# power-v5v5n.net
KiCad netlist of a schematic drawn in Altium Designer
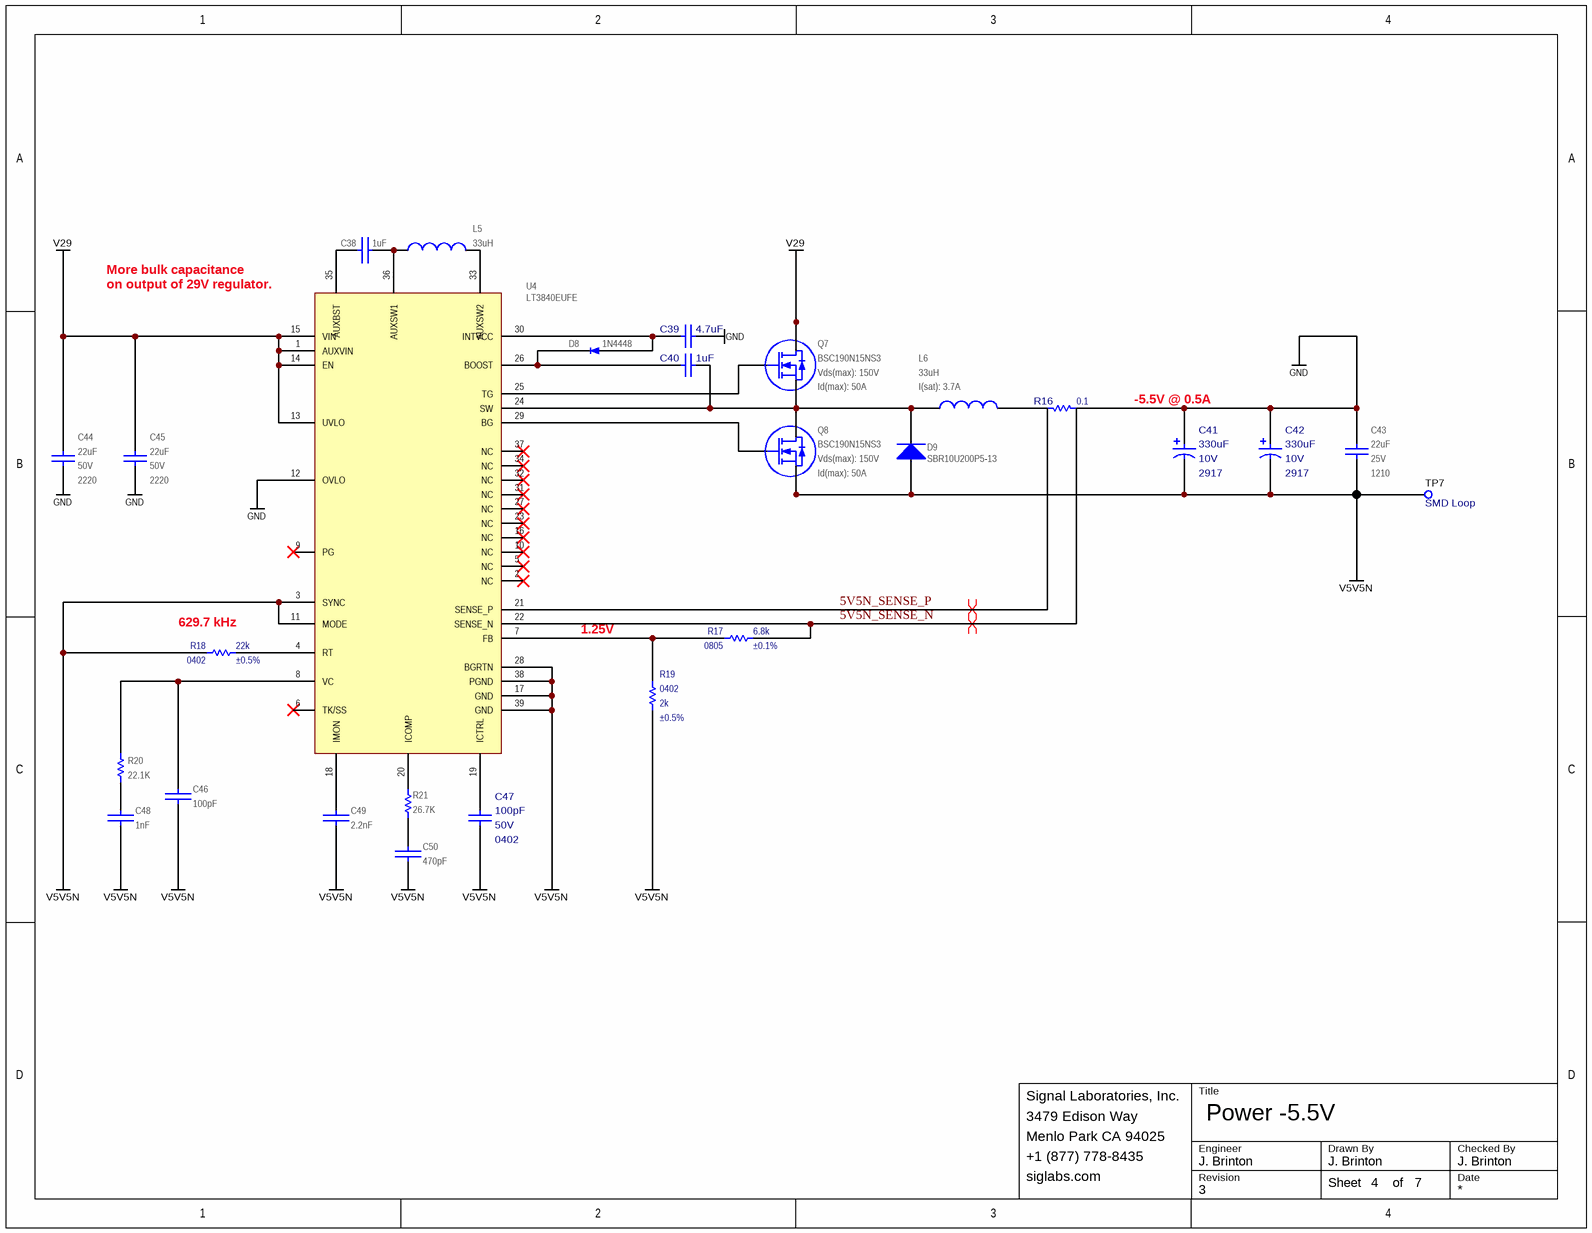
[diagram p0: power-v5v5n.SchDoc]

(export (version "E")
  (design (tool "Eeschema 10.0.6"))
  (components
    (comp (ref "C38")
      (value "1uF")
      (footprint "CAPC100X50X55L25N")
      (description "Ceramic Capacitor 1uF ±10% 10V X5R 0402")
      (fields (field (name "MANUFACTURER") "Murata") (field (name "TOLERANCE") "±10%"))
      (libsource (lib "*") (part "CAP"))
    )
    (comp (ref "C39")
      (value "4.7uF")
      (footprint "CAPC160X80X90L20NA")
      (description "Ceramic Capacitor 4.7uF ±10% 25V X5R 0603")
      (fields (field (name "MANUFACTURER") "Samsung") (field (name "TOLERANCE") "±10%"))
      (libsource (lib "capacitors") (part "CAP"))
    )
    (comp (ref "C40")
      (value "1uF")
      (footprint "CAPC100X50X55L25N")
      (description "Ceramic Capacitor 1uF ±10% 10V X5R 0402")
      (fields (field (name "MANUFACTURER") "Murata") (field (name "TOLERANCE") "±10%"))
      (libsource (lib "capacitors") (part "CAP"))
    )
    (comp (ref "C41")
      (value "330uF")
      (footprint "CAPPM730X435X310L135X240N")
      (description "Tantalum Capacitor 330uF ±10% 10V 2917")
      (fields
        (field (name "MANUFACTURER") "AVX")
        (field (name "TOLERANCE") "±10%")
        (field (name "PACKAGE") "2917")
        (field (name "VOLTAGE") "10V")
      )
      (libsource (lib "avx") (part "CAP_POL"))
    )
    (comp (ref "C42")
      (value "330uF")
      (footprint "CAPPM730X435X310L135X240N")
      (description "Tantalum Capacitor 330uF ±10% 10V 2917")
      (fields
        (field (name "MANUFACTURER") "AVX")
        (field (name "TOLERANCE") "±10%")
        (field (name "PACKAGE") "2917")
        (field (name "VOLTAGE") "10V")
      )
      (libsource (lib "avx") (part "CAP_POL"))
    )
    (comp (ref "C43")
      (value "22uF")
      (footprint "CAPC320X250X270L50N")
      (description "Ceramic Capacitor 22uF ±10% 25V X7R 1210")
      (fields
        (field (name "MANUFACTURER") "Murata")
        (field (name "TOLERANCE") "±10%")
        (field (name "VOLTAGE") "25V")
        (field (name "PACKAGE") "1210")
      )
      (libsource (lib "generic") (part "CAP"))
    )
    (comp (ref "C44")
      (value "22uF")
      (footprint "CAPC600X500X500L160N")
      (description "Ceramic Capacitor 22uF ±20% 50V X7S Stacked")
      (fields
        (field (name "MANUFACTURER") "TDK")
        (field (name "TOLERANCE") "±20%")
        (field (name "VOLTAGE") "50V")
        (field (name "PACKAGE") "2220")
      )
      (libsource (lib "generic") (part "CAP"))
    )
    (comp (ref "C45")
      (value "22uF")
      (footprint "CAPC600X500X500L160N")
      (description "Ceramic Capacitor 22uF ±20% 50V X7S Stacked")
      (fields
        (field (name "MANUFACTURER") "TDK")
        (field (name "TOLERANCE") "±20%")
        (field (name "VOLTAGE") "50V")
        (field (name "PACKAGE") "2220")
      )
      (libsource (lib "generic") (part "CAP"))
    )
    (comp (ref "C46")
      (value "100pF")
      (footprint "CAPC100X50X55L25N")
      (description "Ceramic Capacitor 100pF ±1% 50V NP0 0402")
      (fields (field (name "MANUFACTURER") "Murata") (field (name "VOLTAGE") "50V"))
      (libsource (lib "*") (part "CAP"))
    )
    (comp (ref "C47")
      (value "100pF")
      (footprint "generic:CAPC100X50X55L25N")
      (description "Ceramic Capacitor 100pF ±10% 50V C0G 0402")
      (fields
        (field (name "MANUFACTURER") "Vishay")
        (field (name "TOLERANCE") "±10%")
        (field (name "PACKAGE") "0402")
        (field (name "VOLTAGE") "50V")
      )
      (libsource (lib "capacitors") (part "CAP"))
    )
    (comp (ref "C48")
      (value "1nF")
      (footprint "CAPC100X50X55L25N")
      (description "Ceramic Capacitor 1nF ±5% 50V NP0 0402")
      (fields (field (name "MANUFACTURER") "Murata") (field (name "VOLTAGE") "50V"))
      (libsource (lib "*") (part "CAP"))
    )
    (comp (ref "C49")
      (value "2.2nF")
      (footprint "CAPC100X50X55L25N")
      (description "Ceramic Capacitor 2.2nF ±5% 25V NP0 0402")
      (fields (field (name "MANUFACTURER") "Kemet") (field (name "TOLERANCE") "±5%"))
      (libsource (lib "*") (part "CAP"))
    )
    (comp (ref "C50")
      (value "470pF")
      (footprint "CAPC100X50X55L25N")
      (description "Ceramic Capacitor 470pF ±5% 50V X7R 0402")
      (fields (field (name "MANUFACTURER") "Murata") (field (name "VOLTAGE") "50V"))
      (libsource (lib "*") (part "CAP"))
    )
    (comp (ref "D8")
      (value "1N4448HWS-7-F")
      (footprint "diodes_inc:SOD323")
      (description "Schottky Diode 80V 250mA SOD323")
      (fields (field (name "MANUFACTURER") "Diodes Inc") (field (name "ALTERNATIVE P/N") "1N4448"))
      (libsource (lib "diodes_inc") (part "1N4448HWS-7-F"))
    )
    (comp (ref "D9")
      (value "SBR10U200P5-13")
      (footprint "DIODES_POWERDI5")
      (description "Schottky Diode 200V 10A SMD")
      (fields (field (name "MANUFACTURER") "Diodes Inc"))
      (libsource (lib "diodes_inc") (part "PDS5100H"))
    )
    (comp (ref "L5")
      (value "33uH")
      (footprint "coilcraft:ME3220")
      (description "Inductor 33uH ±10% 500mA SMD")
      (fields (field (name "MANUFACTURER") "Coilcraft") (field (name "TOLERANCE") "±10%"))
      (libsource (lib "CamBoard_Pico_70.19K") (part "COIL"))
    )
    (comp (ref "L6")
      (value "33uH")
      (footprint "coilcraft:XAL6060")
      (description "Inductor 33uH,3.7A(sat), SMD")
      (fields
        (field (name "MANUFACTURER") "Coilcraft")
        (field (name "I(SAT)") "3.7A")
        (field (name "Comment") "XAL6060-333ME")
      )
      (libsource (lib "CamBoard_Pico_70.19K") (part "COIL"))
    )
    (comp (ref "Q7")
      (value "BSC190N15NS3")
      (footprint "TDSON-8")
      (description "MOSFET N-Channel Enhancement Mode")
      (fields
        (field (name "MANUFACTURER") "Infineon")
        (field (name "VDS(MAX)") "150V")
        (field (name "ID(MAX)") "50A")
      )
      (libsource (lib "infinion") (part "BSC190N15NS3"))
    )
    (comp (ref "Q8")
      (value "BSC190N15NS3")
      (footprint "TDSON-8")
      (description "MOSFET N-Channel Enhancement Mode")
      (fields
        (field (name "MANUFACTURER") "Infineon")
        (field (name "VDS(MAX)") "150V")
        (field (name "ID(MAX)") "50A")
      )
      (libsource (lib "infinion") (part "BSC190N15NS3"))
    )
    (comp (ref "R16")
      (value "0.1")
      (footprint "susumu:KRL3216T4")
      (description "Current Sense Resistor 100 mOhms +/-1% SMD 4-Terminal")
      (fields (field (name "TOLERANCE") "±1%") (field (name "MANUFACTURER") "Susumu"))
      (libsource (lib "susumu") (part "KRL3216T4A-M-R009-F"))
    )
    (comp (ref "R17")
      (value "6.8k")
      (footprint "RESC2012X70N")
      (description "Thin Film Resistor 6.8k +/-0.1% SMD 0805")
      (fields
        (field (name "TOLERANCE") "±0.1%")
        (field (name "MANUFACTURER") "Susumu")
        (field (name "PACKAGE") "0805")
        (field (name "Comment") "RG2012P-682-B-T5")
      )
      (libsource (lib "generic") (part "RES"))
    )
    (comp (ref "R18")
      (value "22k")
      (footprint "RESC1005X40N")
      (description "Thin Film Resistor 22k +/-0.5% SMD 0402")
      (fields
        (field (name "TOLERANCE") "±0.5%")
        (field (name "MANUFACTURER") "Susumu")
        (field (name "PACKAGE") "0402")
        (field (name "Comment") "RR0510P-223-D")
      )
      (libsource (lib "generic") (part "RES"))
    )
    (comp (ref "R19")
      (value "2k")
      (footprint "RESC1005X40N")
      (description "Thin Film Resistor 2k +/-0.5% SMD 0402")
      (fields
        (field (name "TOLERANCE") "±0.5%")
        (field (name "MANUFACTURER") "Susumu")
        (field (name "PACKAGE") "0402")
        (field (name "Comment") "RR0510P-202-D")
      )
      (libsource (lib "generic") (part "RES"))
    )
    (comp (ref "R20")
      (value "22.1K")
      (footprint "generic:RESC1005X40N")
      (description "Thick Film Resistor 22.1k ±1% 0402")
      (fields (field (name "MANUFACTURER") "Panasonic") (field (name "TOLERANCE") "±1%"))
      (libsource (lib "Graviton") (part "RES 0402"))
    )
    (comp (ref "R21")
      (value "26.7K")
      (footprint "generic:RESC1005X40N")
      (description "Thick Film Resistor 26.7k ±1% 0402")
      (fields (field (name "MANUFACTURER") "Panasonic") (field (name "TOLERANCE") "±1%"))
      (libsource (lib "Graviton") (part "RES 0402"))
    )
    (comp (ref "TP7")
      (value "5015")
      (footprint "keystone:5015")
      (description "Test Point SMD")
      (fields (field (name "MANUFACTURER") "Keystone") (field (name "NOTES") "SMD Loop"))
      (libsource (lib "generic") (part "TEST_POINT_SMD_50"))
    )
    (comp (ref "U4")
      (value "LT3840EUFE")
      (footprint "linear:QFN39P40_600X400X80L40X20T465X265N")
      (description "Synchronous Regulator Controller")
      (fields (field (name "MANUFACTURER") "Linear Technology"))
      (libsource (lib "linear") (part "LT3840EUFE"))
    )
  )
  (nets
    (net (code "1") (name "/5V5N_SENSE_N") (class "Default")
      (node (ref "R16") (pin "4") (pinfunction "4_4") (pintype "passive"))
      (node (ref "R17") (pin "1") (pinfunction "1_1") (pintype "passive"))
      (node (ref "U4") (pin "22") (pinfunction "SENSE_N_22") (pintype "passive"))
    )
    (net (code "2") (name "/5V5N_SENSE_P") (class "Default")
      (node (ref "R16") (pin "3") (pinfunction "3_3") (pintype "passive"))
      (node (ref "U4") (pin "21") (pinfunction "SENSE_P_21") (pintype "passive"))
    )
    (net (code "3") (name "GND") (class "Default")
      (node (ref "C39") (pin "2") (pinfunction "2_2") (pintype "passive"))
      (node (ref "C41") (pin "1") (pinfunction "1_1") (pintype "passive"))
      (node (ref "C42") (pin "1") (pinfunction "1_1") (pintype "passive"))
      (node (ref "C43") (pin "2") (pinfunction "2_2") (pintype "passive"))
      (node (ref "C44") (pin "1") (pinfunction "1_1") (pintype "passive"))
      (node (ref "C45") (pin "1") (pinfunction "1_1") (pintype "passive"))
      (node (ref "R16") (pin "2") (pinfunction "2_2") (pintype "passive"))
      (node (ref "U4") (pin "12") (pinfunction "OVLO_12") (pintype "passive"))
    )
    (net (code "4") (name "Net-(C48-Pad1)") (class "Default")
      (node (ref "C48") (pin "1") (pinfunction "1_1") (pintype "passive"))
      (node (ref "R20") (pin "1") (pinfunction "1_1") (pintype "passive"))
    )
    (net (code "5") (name "Net-(C50-Pad2)") (class "Default")
      (node (ref "C50") (pin "2") (pinfunction "2_2") (pintype "passive"))
      (node (ref "R21") (pin "2") (pinfunction "2_2") (pintype "passive"))
    )
    (net (code "6") (name "Net-(L6-Pad2)") (class "Default")
      (node (ref "L6") (pin "2") (pinfunction "2_2") (pintype "passive"))
      (node (ref "R16") (pin "1") (pinfunction "1_1") (pintype "passive"))
    )
    (net (code "7") (name "Net-(Q7-G)") (class "Default")
      (node (ref "Q7") (pin "4") (pinfunction "G_4") (pintype "passive"))
      (node (ref "U4") (pin "25") (pinfunction "TG_25") (pintype "passive"))
    )
    (net (code "8") (name "Net-(Q8-G)") (class "Default")
      (node (ref "Q8") (pin "4") (pinfunction "G_4") (pintype "passive"))
      (node (ref "U4") (pin "29") (pinfunction "BG_29") (pintype "passive"))
    )
    (net (code "9") (name "Net-(U4-AUXBST)") (class "Default")
      (node (ref "C38") (pin "2") (pinfunction "2_2") (pintype "passive"))
      (node (ref "U4") (pin "35") (pinfunction "AUXBST_35") (pintype "passive"))
    )
    (net (code "10") (name "Net-(U4-AUXSW1)") (class "Default")
      (node (ref "C38") (pin "1") (pinfunction "1_1") (pintype "passive"))
      (node (ref "L5") (pin "1") (pinfunction "1_1") (pintype "passive"))
      (node (ref "U4") (pin "36") (pinfunction "AUXSW1_36") (pintype "passive"))
    )
    (net (code "11") (name "Net-(U4-AUXSW2)") (class "Default")
      (node (ref "L5") (pin "2") (pinfunction "2_2") (pintype "passive"))
      (node (ref "U4") (pin "33") (pinfunction "AUXSW2_33") (pintype "passive"))
    )
    (net (code "12") (name "Net-(U4-BOOST)") (class "Default")
      (node (ref "C40") (pin "1") (pinfunction "1_1") (pintype "passive"))
      (node (ref "D8") (pin "K") (pinfunction "K_K") (pintype "passive"))
      (node (ref "U4") (pin "26") (pinfunction "BOOST_26") (pintype "passive"))
    )
    (net (code "13") (name "Net-(U4-FB)") (class "Default")
      (node (ref "R17") (pin "2") (pinfunction "2_2") (pintype "passive"))
      (node (ref "R19") (pin "2") (pinfunction "2_2") (pintype "passive"))
      (node (ref "U4") (pin "7") (pinfunction "FB_7") (pintype "passive"))
    )
    (net (code "14") (name "Net-(U4-ICOMP)") (class "Default")
      (node (ref "R21") (pin "1") (pinfunction "1_1") (pintype "passive"))
      (node (ref "U4") (pin "20") (pinfunction "ICOMP_20") (pintype "passive"))
    )
    (net (code "15") (name "Net-(U4-ICTRL)") (class "Default")
      (node (ref "C47") (pin "1") (pinfunction "1_1") (pintype "passive"))
      (node (ref "U4") (pin "19") (pinfunction "ICTRL_19") (pintype "passive"))
    )
    (net (code "16") (name "Net-(U4-IMON)") (class "Default")
      (node (ref "C49") (pin "1") (pinfunction "1_1") (pintype "passive"))
      (node (ref "U4") (pin "18") (pinfunction "IMON_18") (pintype "passive"))
    )
    (net (code "17") (name "Net-(U4-INTVCC)") (class "Default")
      (node (ref "C39") (pin "1") (pinfunction "1_1") (pintype "passive"))
      (node (ref "D8") (pin "A") (pinfunction "A_A") (pintype "passive"))
      (node (ref "U4") (pin "30") (pinfunction "INTVCC_30") (pintype "passive"))
    )
    (net (code "18") (name "Net-(U4-RT)") (class "Default")
      (node (ref "R18") (pin "1") (pinfunction "1_1") (pintype "passive"))
      (node (ref "U4") (pin "4") (pinfunction "RT_4") (pintype "passive"))
    )
    (net (code "19") (name "Net-(U4-SW)") (class "Default")
      (node (ref "C40") (pin "2") (pinfunction "2_2") (pintype "passive"))
      (node (ref "D9") (pin "K") (pinfunction "K_K") (pintype "passive"))
      (node (ref "L6") (pin "1") (pinfunction "1_1") (pintype "passive"))
      (node (ref "Q7") (pin "1") (pinfunction "S_1") (pintype "passive"))
      (node (ref "Q7") (pin "2") (pinfunction "S_2") (pintype "passive"))
      (node (ref "Q7") (pin "3") (pinfunction "S_3") (pintype "passive"))
      (node (ref "Q8") (pin "5") (pinfunction "D_5") (pintype "passive"))
      (node (ref "Q8") (pin "6") (pinfunction "D_6") (pintype "passive"))
      (node (ref "Q8") (pin "7") (pinfunction "D_7") (pintype "passive"))
      (node (ref "Q8") (pin "8") (pinfunction "D_8") (pintype "passive"))
      (node (ref "Q8") (pin "9") (pinfunction "D_9") (pintype "passive"))
      (node (ref "U4") (pin "24") (pinfunction "SW_24") (pintype "passive"))
    )
    (net (code "20") (name "Net-(U4-VC)") (class "Default")
      (node (ref "C46") (pin "2") (pinfunction "2_2") (pintype "passive"))
      (node (ref "R20") (pin "2") (pinfunction "2_2") (pintype "passive"))
      (node (ref "U4") (pin "8") (pinfunction "VC_8") (pintype "passive"))
    )
    (net (code "21") (name "V5V5N") (class "Default")
      (node (ref "C41") (pin "2") (pinfunction "2_2") (pintype "passive"))
      (node (ref "C42") (pin "2") (pinfunction "2_2") (pintype "passive"))
      (node (ref "C43") (pin "1") (pinfunction "1_1") (pintype "passive"))
      (node (ref "C46") (pin "1") (pinfunction "1_1") (pintype "passive"))
      (node (ref "C47") (pin "2") (pinfunction "2_2") (pintype "passive"))
      (node (ref "C48") (pin "2") (pinfunction "2_2") (pintype "passive"))
      (node (ref "C49") (pin "2") (pinfunction "2_2") (pintype "passive"))
      (node (ref "C50") (pin "1") (pinfunction "1_1") (pintype "passive"))
      (node (ref "D9") (pin "A") (pinfunction "A_A") (pintype "power_in"))
      (node (ref "Q8") (pin "1") (pinfunction "S_1") (pintype "passive"))
      (node (ref "Q8") (pin "2") (pinfunction "S_2") (pintype "passive"))
      (node (ref "Q8") (pin "3") (pinfunction "S_3") (pintype "passive"))
      (node (ref "R18") (pin "2") (pinfunction "2_2") (pintype "passive"))
      (node (ref "R19") (pin "1") (pinfunction "1_1") (pintype "passive"))
      (node (ref "TP7") (pin "1") (pinfunction "1_1") (pintype "passive"))
      (node (ref "U4") (pin "11") (pinfunction "MODE_11") (pintype "passive"))
      (node (ref "U4") (pin "17") (pinfunction "GND_17") (pintype "passive"))
      (node (ref "U4") (pin "28") (pinfunction "BGRTN_28") (pintype "passive"))
      (node (ref "U4") (pin "3") (pinfunction "SYNC_3") (pintype "passive"))
      (node (ref "U4") (pin "38") (pinfunction "PGND_38") (pintype "passive"))
      (node (ref "U4") (pin "39") (pinfunction "GND_39") (pintype "passive"))
    )
    (net (code "22") (name "V29") (class "Default")
      (node (ref "C44") (pin "2") (pinfunction "2_2") (pintype "passive"))
      (node (ref "C45") (pin "2") (pinfunction "2_2") (pintype "passive"))
      (node (ref "Q7") (pin "5") (pinfunction "D_5") (pintype "passive"))
      (node (ref "Q7") (pin "6") (pinfunction "D_6") (pintype "passive"))
      (node (ref "Q7") (pin "7") (pinfunction "D_7") (pintype "passive"))
      (node (ref "Q7") (pin "8") (pinfunction "D_8") (pintype "passive"))
      (node (ref "Q7") (pin "9") (pinfunction "D_9") (pintype "passive"))
      (node (ref "U4") (pin "1") (pinfunction "AUXVIN_1") (pintype "passive"))
      (node (ref "U4") (pin "13") (pinfunction "UVLO_13") (pintype "passive"))
      (node (ref "U4") (pin "14") (pinfunction "EN_14") (pintype "passive"))
      (node (ref "U4") (pin "15") (pinfunction "VIN_15") (pintype "passive"))
    )
    (net (code "23") (name "unconnected-(U4-NC-Pad2)") (class "Default")
      (node (ref "U4") (pin "2") (pinfunction "NC_2") (pintype "passive+no_connect"))
    )
    (net (code "24") (name "unconnected-(U4-NC-Pad5)") (class "Default")
      (node (ref "U4") (pin "5") (pinfunction "NC_5") (pintype "passive+no_connect"))
    )
    (net (code "25") (name "unconnected-(U4-NC-Pad10)") (class "Default")
      (node (ref "U4") (pin "10") (pinfunction "NC_10") (pintype "passive+no_connect"))
    )
    (net (code "26") (name "unconnected-(U4-NC-Pad16)") (class "Default")
      (node (ref "U4") (pin "16") (pinfunction "NC_16") (pintype "passive+no_connect"))
    )
    (net (code "27") (name "unconnected-(U4-NC-Pad23)") (class "Default")
      (node (ref "U4") (pin "23") (pinfunction "NC_23") (pintype "passive+no_connect"))
    )
    (net (code "28") (name "unconnected-(U4-NC-Pad27)") (class "Default")
      (node (ref "U4") (pin "27") (pinfunction "NC_27") (pintype "passive+no_connect"))
    )
    (net (code "29") (name "unconnected-(U4-NC-Pad31)") (class "Default")
      (node (ref "U4") (pin "31") (pinfunction "NC_31") (pintype "passive+no_connect"))
    )
    (net (code "30") (name "unconnected-(U4-NC-Pad32)") (class "Default")
      (node (ref "U4") (pin "32") (pinfunction "NC_32") (pintype "passive+no_connect"))
    )
    (net (code "31") (name "unconnected-(U4-NC-Pad34)") (class "Default")
      (node (ref "U4") (pin "34") (pinfunction "NC_34") (pintype "passive+no_connect"))
    )
    (net (code "32") (name "unconnected-(U4-NC-Pad37)") (class "Default")
      (node (ref "U4") (pin "37") (pinfunction "NC_37") (pintype "passive+no_connect"))
    )
    (net (code "33") (name "unconnected-(U4-PG-Pad9)") (class "Default")
      (node (ref "U4") (pin "9") (pinfunction "PG_9") (pintype "passive+no_connect"))
    )
    (net (code "34") (name "unconnected-(U4-TK{slash}SS-Pad6)") (class "Default")
      (node (ref "U4") (pin "6") (pinfunction "TK/SS_6") (pintype "passive+no_connect"))
    )
  )
)
